# AMS_Slave.net
KiCad netlist of a schematic drawn in Altium Designer
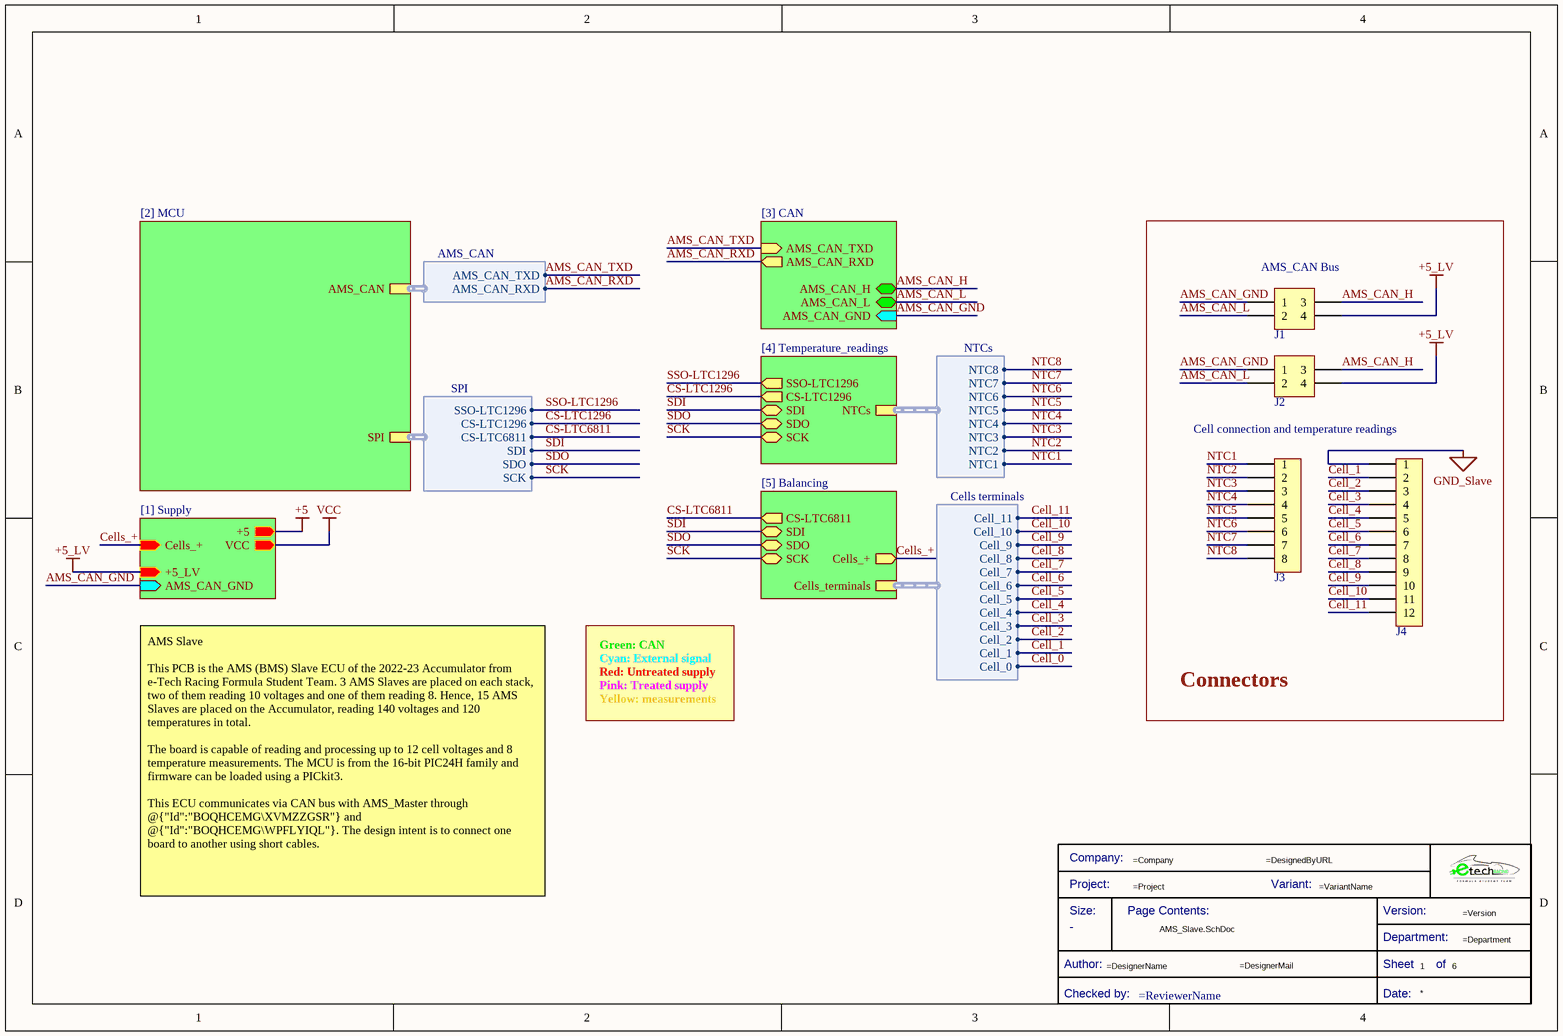
[diagram p0: AMS_Slave.SchDoc]

(export (version "E")
  (design (tool "Eeschema 10.0.6"))
  (components
    (comp (ref "*")
      (value "Title Block_template")
      (description "Standard Title Block")
      (fields (field (name "SIZE") "-"))
      (libsource (lib "e-Tech_Racing") (part "Title Block_template"))
    )
    (comp (ref "J1")
      (value "430450412")
      (footprint "J_MicroFit_2x2_v")
      (description "Header 2 Row Vertical Polarizing Peg 4 Pin Tin Plate SMT/Glow Wire Kinked Leads")
      (fields (field (name ".CREATOR") "DR"))
      (libsource (lib "Electromechanical") (part "J_MicroFit_2x2"))
    )
    (comp (ref "J2")
      (value "430450412")
      (footprint "J_MicroFit_2x2_v")
      (description "Header 2 Row Vertical Polarizing Peg 4 Pin Tin Plate SMT/Glow Wire Kinked Leads")
      (fields (field (name ".CREATOR") "DR"))
      (libsource (lib "Electromechanical") (part "J_MicroFit_2x2"))
    )
    (comp (ref "J3")
      (value "J_MicroFit_1x8_V")
      (footprint "J_MicroFit_1x8_V")
      (description "Conn Wire to Board HDR 8 POS 3mm Solder ST Top Entry Thru-Hole Micro-Fit 3.0™ Tray")
      (fields (field (name ".CREATOR") "DR"))
      (libsource (lib "Electromechanical") (part "J_MicroFit_1x8_V"))
    )
    (comp (ref "J4")
      (value "J_MicroFit_1x12_V")
      (footprint "J_MicroFit_1x12_V")
      (description "Conn Power HDR 12 POS 3mm Solder ST Thru-Hole 12 Terminal 1 Port Micro-Fit 3.0™ Tray")
      (libsource (lib "Electromechanical") (part "J_MicroFit_1x12_V"))
    )
  )
  (nets
    (net (code "7") (name "+5_LV") (class "Default")
      (node (ref "J1") (pin "4") (pinfunction "4_4") (pintype "passive"))
      (node (ref "J2") (pin "4") (pinfunction "4_4") (pintype "passive"))
    )
    (net (code "8") (name "/AMS_CAN_GND") (class "Default")
      (node (ref "J1") (pin "1") (pinfunction "1_1") (pintype "passive"))
      (node (ref "J2") (pin "1") (pinfunction "1_1") (pintype "passive"))
    )
    (net (code "9") (name "/AMS_CAN_H") (class "Default")
      (node (ref "J1") (pin "3") (pinfunction "3_3") (pintype "passive"))
      (node (ref "J2") (pin "3") (pinfunction "3_3") (pintype "passive"))
    )
    (net (code "10") (name "/AMS_CAN_L") (class "Default")
      (node (ref "J1") (pin "2") (pinfunction "2_2") (pintype "passive"))
      (node (ref "J2") (pin "2") (pinfunction "2_2") (pintype "passive"))
    )
    (net (code "16") (name "/Cell_1") (class "Default")
      (node (ref "J4") (pin "2") (pinfunction "2_2") (pintype "passive"))
    )
    (net (code "17") (name "/Cell_2") (class "Default")
      (node (ref "J4") (pin "3") (pinfunction "3_3") (pintype "passive"))
    )
    (net (code "18") (name "/Cell_3") (class "Default")
      (node (ref "J4") (pin "4") (pinfunction "4_4") (pintype "passive"))
    )
    (net (code "19") (name "/Cell_4") (class "Default")
      (node (ref "J4") (pin "5") (pinfunction "5_5") (pintype "passive"))
    )
    (net (code "20") (name "/Cell_5") (class "Default")
      (node (ref "J4") (pin "6") (pinfunction "6_6") (pintype "passive"))
    )
    (net (code "21") (name "/Cell_6") (class "Default")
      (node (ref "J4") (pin "7") (pinfunction "7_7") (pintype "passive"))
    )
    (net (code "22") (name "/Cell_7") (class "Default")
      (node (ref "J4") (pin "8") (pinfunction "8_8") (pintype "passive"))
    )
    (net (code "23") (name "/Cell_8") (class "Default")
      (node (ref "J4") (pin "9") (pinfunction "9_9") (pintype "passive"))
    )
    (net (code "24") (name "/Cell_9") (class "Default")
      (node (ref "J4") (pin "10") (pinfunction "10_10") (pintype "passive"))
    )
    (net (code "25") (name "/Cell_10") (class "Default")
      (node (ref "J4") (pin "11") (pinfunction "11_11") (pintype "passive"))
    )
    (net (code "26") (name "/Cell_11") (class "Default")
      (node (ref "J4") (pin "12") (pinfunction "12_12") (pintype "passive"))
    )
    (net (code "28") (name "/NTC1") (class "Default")
      (node (ref "J3") (pin "1") (pinfunction "1_1") (pintype "passive"))
    )
    (net (code "29") (name "/NTC2") (class "Default")
      (node (ref "J3") (pin "2") (pinfunction "2_2") (pintype "passive"))
    )
    (net (code "30") (name "/NTC3") (class "Default")
      (node (ref "J3") (pin "3") (pinfunction "3_3") (pintype "passive"))
    )
    (net (code "31") (name "/NTC4") (class "Default")
      (node (ref "J3") (pin "4") (pinfunction "4_4") (pintype "passive"))
    )
    (net (code "32") (name "/NTC5") (class "Default")
      (node (ref "J3") (pin "5") (pinfunction "5_5") (pintype "passive"))
    )
    (net (code "33") (name "/NTC6") (class "Default")
      (node (ref "J3") (pin "6") (pinfunction "6_6") (pintype "passive"))
    )
    (net (code "34") (name "/NTC7") (class "Default")
      (node (ref "J3") (pin "7") (pinfunction "7_7") (pintype "passive"))
    )
    (net (code "35") (name "/NTC8") (class "Default")
      (node (ref "J3") (pin "8") (pinfunction "8_8") (pintype "passive"))
    )
    (net (code "44") (name "GND_Slave") (class "Default")
      (node (ref "J4") (pin "1") (pinfunction "1_1") (pintype "passive"))
    )
  )
)
